# PSAT.net
KiCad netlist of a schematic drawn in Altium Designer
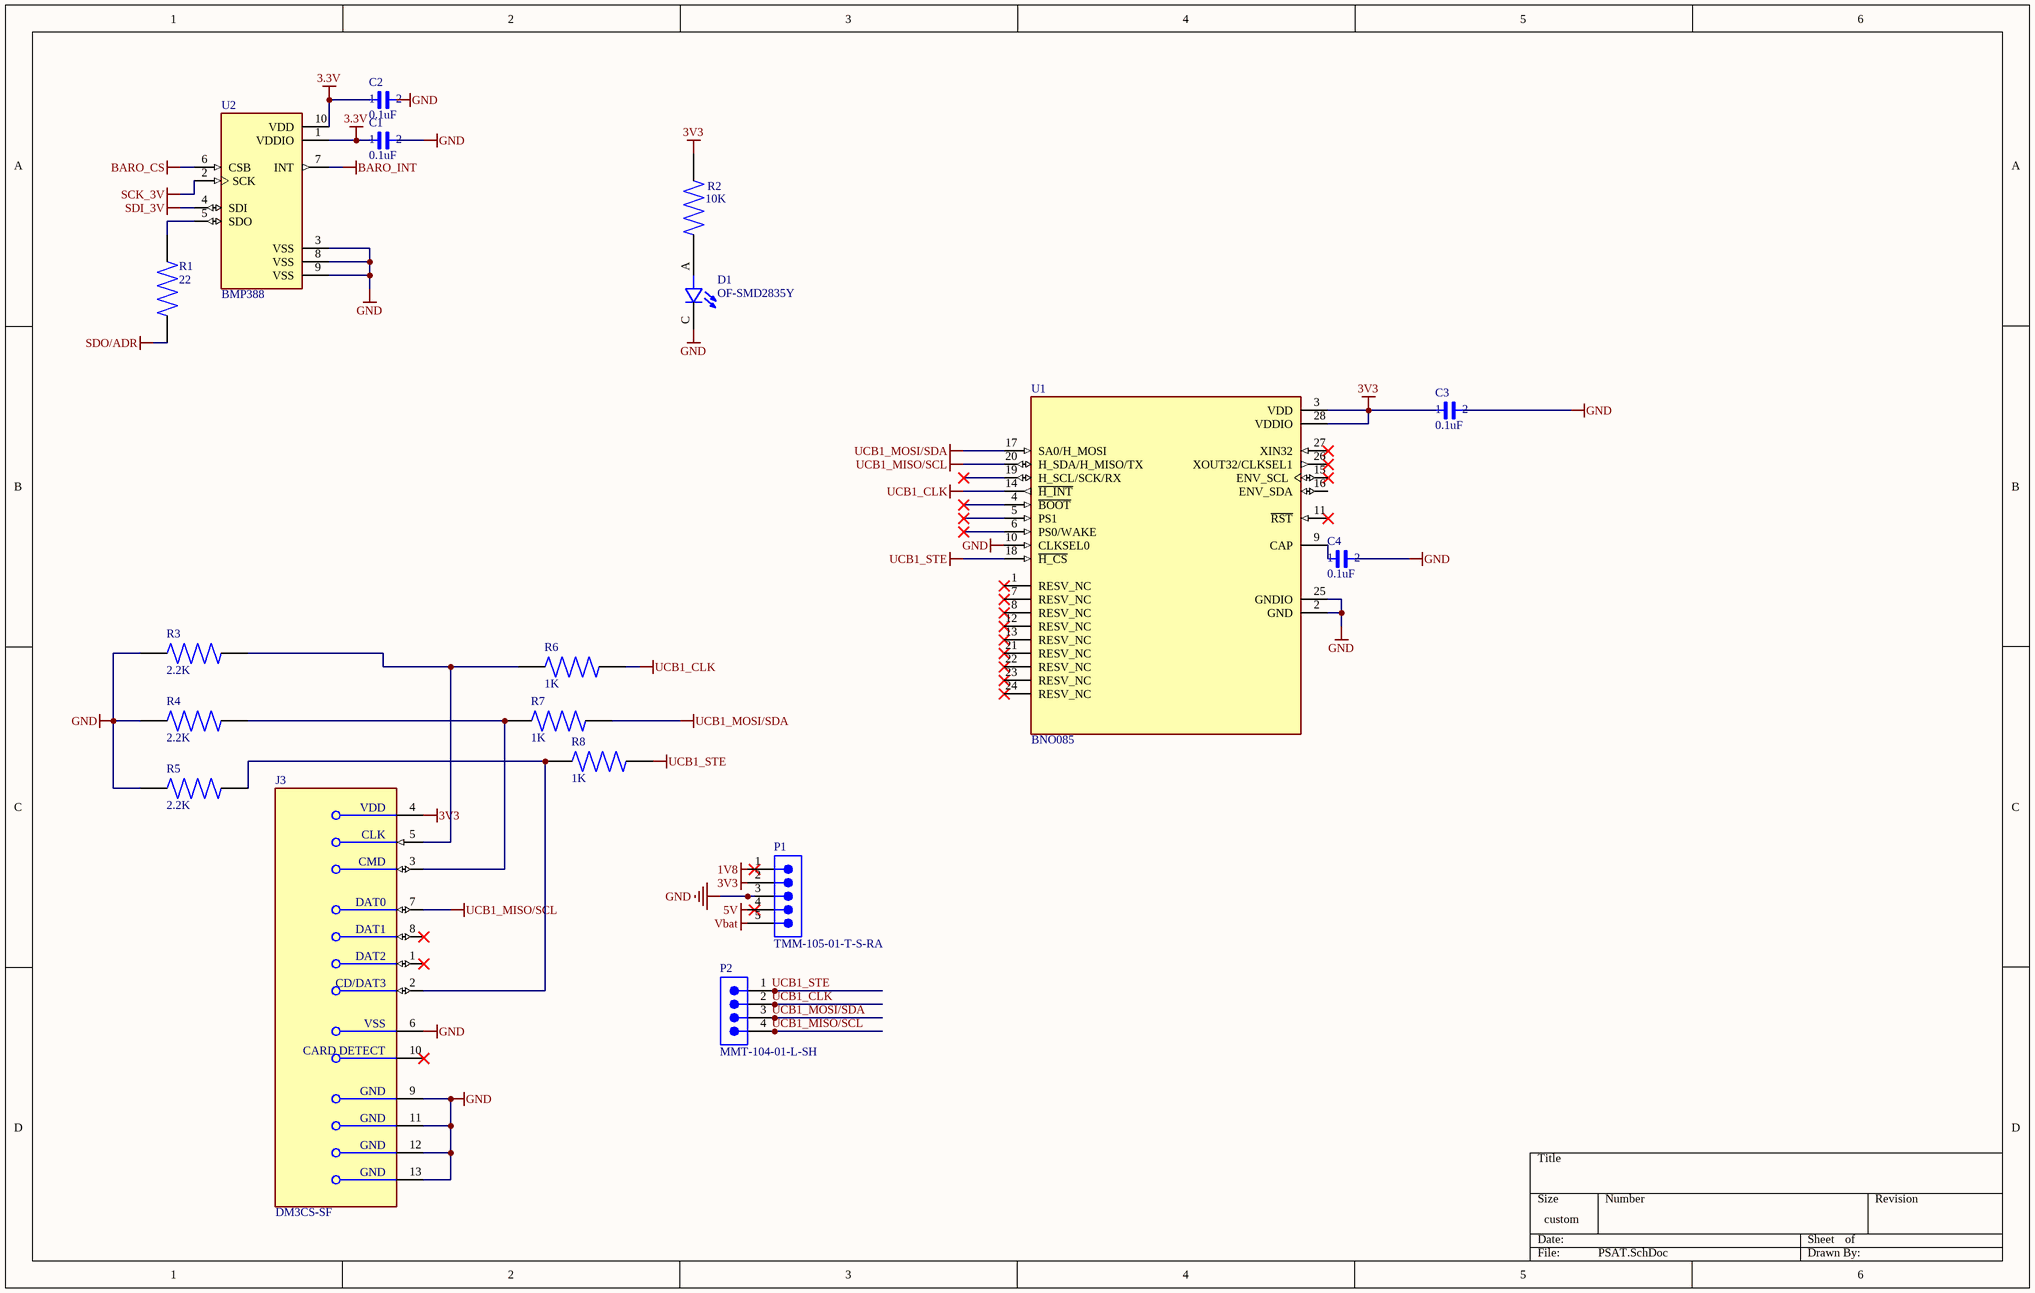
[diagram p0: PSAT.SchDoc]

(export (version "E")
  (design (tool "Eeschema 10.0.6"))
  (components
    (comp (ref "C1")
      (value "0.1uF")
      (footprint "0603")
      (description "0 Ohms Jumper 0.1W, 1/10W Chip Resistor 0603 (1608 Metric) Moisture Resistant Thick Film")
      (fields (field (name "MF") "Yageo") (field (name "MP") "C0603"))
      (libsource (lib "C0603") (part "C0603"))
    )
    (comp (ref "C2")
      (value "0.1uF")
      (footprint "0603")
      (description "0 Ohms Jumper 0.1W, 1/10W Chip Resistor 0603 (1608 Metric) Moisture Resistant Thick Film")
      (fields (field (name "MF") "Yageo") (field (name "MP") "C0603"))
      (libsource (lib "C0603") (part "C0603"))
    )
    (comp (ref "C3")
      (value "0.1uF")
      (footprint "0603")
      (description "0 Ohms Jumper 0.1W, 1/10W Chip Resistor 0603 (1608 Metric) Moisture Resistant Thick Film")
      (fields (field (name "MF") "Yageo") (field (name "MP") "C0603"))
      (libsource (lib "C0603") (part "C0603"))
    )
    (comp (ref "C4")
      (value "0.1uF")
      (footprint "0603")
      (description "0 Ohms Jumper 0.1W, 1/10W Chip Resistor 0603 (1608 Metric) Moisture Resistant Thick Film")
      (fields (field (name "MF") "Yageo") (field (name "MP") "C0603"))
      (libsource (lib "C0603") (part "C0603"))
    )
    (comp (ref "D1")
      (value "OF-SMD2835Y")
      (footprint "LED_OF-SMD2835Y")
      (description "LED; SMD; 2835, PLCC2; yellow; 2200-2800mcd; 2.8x3.5x0.75mm; 120Â°")
      (libsource (lib "OF-SMD2835Y") (part "OF-SMD2835Y"))
    )
    (comp (ref "J3")
      (value "DM3CS-SF")
      (footprint "FP-DM3CS-SF-MFG")
      (description "CONN MICRO SD CARD HINGED TYPE")
      (libsource (lib "Altium Content Vault") (part "bac915de5305cfdd1ca301aae530106"))
    )
    (comp (ref "P1")
      (value "TMM-105-01-T-S-RA")
      (footprint "SMTC-TMM-105-01-X-S-RA")
      (description "Low Profile Through-Hole Header, Right Angle, -55 to 105 degC, 2 mm Pitch, 5-Pin, Male, RoHS")
      (fields (field (name "MANUFACTURER") "Samtec"))
      (libsource (lib "Altium Content Vault") (part "SMTC-TMM-105-01-X-S-RA"))
    )
    (comp (ref "P2")
      (value "MMT-104-01-L-SH")
      (footprint "SMTC-MMT-104-01-X-SH")
      (description "Horizontal Surface Mount Header, -55 to 125 degC, 2 mm Pitch, 4-Pin, Male, RoHS")
      (fields (field (name "MANUFACTURER") "Samtec"))
      (libsource (lib "Altium Content Vault") (part "SMTC-MMT-104-X-X-SH"))
    )
    (comp (ref "R1")
      (value "22")
      (footprint "RESC1607X60N")
      (description "0 Ohms Jumper 0.1W, 1/10W Chip Resistor 0603 (1608 Metric) Moisture Resistant Thick Film")
      (fields (field (name "MF") "Yageo") (field (name "MP") "RC0603JR-070RL"))
      (libsource (lib "RC0603JR-070RL") (part "RC0603JR-070RL"))
    )
    (comp (ref "R2")
      (value "10K")
      (footprint "RESC1607X60N")
      (description "0 Ohms Jumper 0.1W, 1/10W Chip Resistor 0603 (1608 Metric) Moisture Resistant Thick Film")
      (fields (field (name "MF") "Yageo") (field (name "MP") "RC0603JR-070RL"))
      (libsource (lib "RC0603JR-070RL") (part "RC0603JR-070RL"))
    )
    (comp (ref "R3")
      (value "2.2K")
      (footprint "RESC1607X60N")
      (description "0 Ohms Jumper 0.1W, 1/10W Chip Resistor 0603 (1608 Metric) Moisture Resistant Thick Film")
      (fields (field (name "MF") "Yageo") (field (name "MP") "RC0603JR-070RL"))
      (libsource (lib "RC0603JR-070RL") (part "RC0603JR-070RL"))
    )
    (comp (ref "R4")
      (value "2.2K")
      (footprint "RESC1607X60N")
      (description "0 Ohms Jumper 0.1W, 1/10W Chip Resistor 0603 (1608 Metric) Moisture Resistant Thick Film")
      (fields (field (name "MF") "Yageo") (field (name "MP") "RC0603JR-070RL"))
      (libsource (lib "RC0603JR-070RL") (part "RC0603JR-070RL"))
    )
    (comp (ref "R5")
      (value "2.2K")
      (footprint "RESC1607X60N")
      (description "0 Ohms Jumper 0.1W, 1/10W Chip Resistor 0603 (1608 Metric) Moisture Resistant Thick Film")
      (fields (field (name "MF") "Yageo") (field (name "MP") "RC0603JR-070RL"))
      (libsource (lib "RC0603JR-070RL") (part "RC0603JR-070RL"))
    )
    (comp (ref "R6")
      (value "1K")
      (footprint "RESC1607X60N")
      (description "0 Ohms Jumper 0.1W, 1/10W Chip Resistor 0603 (1608 Metric) Moisture Resistant Thick Film")
      (fields (field (name "MF") "Yageo") (field (name "MP") "RC0603JR-070RL"))
      (libsource (lib "RC0603JR-070RL") (part "RC0603JR-070RL"))
    )
    (comp (ref "R7")
      (value "1K")
      (footprint "RESC1607X60N")
      (description "0 Ohms Jumper 0.1W, 1/10W Chip Resistor 0603 (1608 Metric) Moisture Resistant Thick Film")
      (fields (field (name "MF") "Yageo") (field (name "MP") "RC0603JR-070RL"))
      (libsource (lib "RC0603JR-070RL") (part "RC0603JR-070RL"))
    )
    (comp (ref "R8")
      (value "1K")
      (footprint "RESC1607X60N")
      (description "0 Ohms Jumper 0.1W, 1/10W Chip Resistor 0603 (1608 Metric) Moisture Resistant Thick Film")
      (fields (field (name "MF") "Yageo") (field (name "MP") "RC0603JR-070RL"))
      (libsource (lib "RC0603JR-070RL") (part "RC0603JR-070RL"))
    )
    (comp (ref "U1")
      (value "BNO085")
      (footprint "IC_BNO085")
      (description "Accelerometer, Gyroscope, Magnetometer, 9 Axis Sensor IÂ²C, SPI, UART Output")
      (fields (field (name "MF") "Hillcrest Laboratories,"))
      (libsource (lib "BNO085 (1)") (part "BNO085"))
    )
    (comp (ref "U2")
      (value "BMP388")
      (footprint "PQFN50P200X200X80-10N")
      (description "P-Sensor SPI I2C 1, 25 Bar SMD")
      (libsource (lib "BMP388") (part "BMP388"))
    )
  )
  (nets
    (net (code "2") (name "3.3V") (class "Default")
      (node (ref "C1") (pin "1") (pinfunction "1_1") (pintype "passive"))
      (node (ref "C2") (pin "1") (pinfunction "1_1") (pintype "passive"))
      (node (ref "U2") (pin "1") (pinfunction "VDDIO_1") (pintype "power_in"))
      (node (ref "U2") (pin "10") (pinfunction "VDD_10") (pintype "power_in"))
    )
    (net (code "3") (name "3V3") (class "Default")
      (node (ref "C3") (pin "1") (pinfunction "1_1") (pintype "passive"))
      (node (ref "J3") (pin "4") (pinfunction "VDD_4") (pintype "power_in"))
      (node (ref "R2") (pin "2") (pinfunction "2_2") (pintype "passive"))
      (node (ref "U1") (pin "28") (pinfunction "VDDIO_28") (pintype "power_in"))
      (node (ref "U1") (pin "3") (pinfunction "VDD_3") (pintype "power_in"))
    )
    (net (code "5") (name "BARO_CS") (class "Default")
      (node (ref "U2") (pin "6") (pinfunction "CSB_6") (pintype "input"))
    )
    (net (code "6") (name "BARO_INT") (class "Default")
      (node (ref "U2") (pin "7") (pinfunction "INT_7") (pintype "output"))
    )
    (net (code "7") (name "GND") (class "Default")
      (node (ref "C1") (pin "2") (pinfunction "2_2") (pintype "passive"))
      (node (ref "C2") (pin "2") (pinfunction "2_2") (pintype "passive"))
      (node (ref "C3") (pin "2") (pinfunction "2_2") (pintype "passive"))
      (node (ref "C4") (pin "2") (pinfunction "2_2") (pintype "passive"))
      (node (ref "D1") (pin "C") (pinfunction "C_C") (pintype "passive"))
      (node (ref "J3") (pin "11") (pinfunction "GND_11") (pintype "power_in"))
      (node (ref "J3") (pin "12") (pinfunction "GND_12") (pintype "power_in"))
      (node (ref "J3") (pin "13") (pinfunction "GND_13") (pintype "power_in"))
      (node (ref "J3") (pin "6") (pinfunction "VSS_6") (pintype "power_in"))
      (node (ref "J3") (pin "9") (pinfunction "GND_9") (pintype "power_in"))
      (node (ref "P1") (pin "3") (pinfunction "3_3") (pintype "passive"))
      (node (ref "R3") (pin "2") (pinfunction "2_2") (pintype "passive"))
      (node (ref "R4") (pin "2") (pinfunction "2_2") (pintype "passive"))
      (node (ref "R5") (pin "2") (pinfunction "2_2") (pintype "passive"))
      (node (ref "U1") (pin "10") (pinfunction "CLKSEL0_10") (pintype "input"))
      (node (ref "U1") (pin "2") (pinfunction "GND_2") (pintype "power_in"))
      (node (ref "U1") (pin "25") (pinfunction "GNDIO_25") (pintype "power_in"))
      (node (ref "U2") (pin "3") (pinfunction "VSS_3") (pintype "power_in"))
      (node (ref "U2") (pin "8") (pinfunction "VSS_8") (pintype "power_in"))
      (node (ref "U2") (pin "9") (pinfunction "VSS_9") (pintype "power_in"))
    )
    (net (code "8") (name "Net-(D1-PadA)") (class "Default")
      (node (ref "D1") (pin "A") (pinfunction "A_A") (pintype "passive"))
      (node (ref "R2") (pin "1") (pinfunction "1_1") (pintype "passive"))
    )
    (net (code "9") (name "Net-(J3-CD{slash}DAT3)") (class "Default")
      (node (ref "J3") (pin "2") (pinfunction "CD/DAT3_2") (pintype "bidirectional"))
      (node (ref "R5") (pin "1") (pinfunction "1_1") (pintype "passive"))
      (node (ref "R8") (pin "2") (pinfunction "2_2") (pintype "passive"))
    )
    (net (code "10") (name "Net-(J3-CLK)") (class "Default")
      (node (ref "J3") (pin "5") (pinfunction "CLK_5") (pintype "input"))
      (node (ref "R3") (pin "1") (pinfunction "1_1") (pintype "passive"))
      (node (ref "R6") (pin "2") (pinfunction "2_2") (pintype "passive"))
    )
    (net (code "11") (name "Net-(J3-CMD)") (class "Default")
      (node (ref "J3") (pin "3") (pinfunction "CMD_3") (pintype "bidirectional"))
      (node (ref "R4") (pin "1") (pinfunction "1_1") (pintype "passive"))
      (node (ref "R7") (pin "2") (pinfunction "2_2") (pintype "passive"))
    )
    (net (code "12") (name "Net-(U1-CAP)") (class "Default")
      (node (ref "C4") (pin "1") (pinfunction "1_1") (pintype "passive"))
      (node (ref "U1") (pin "9") (pinfunction "CAP_9") (pintype "passive"))
    )
    (net (code "13") (name "Net-(U2-SDO)") (class "Default")
      (node (ref "R1") (pin "2") (pinfunction "2_2") (pintype "passive"))
      (node (ref "U2") (pin "5") (pinfunction "SDO_5") (pintype "bidirectional"))
    )
    (net (code "14") (name "SCK_3V") (class "Default")
      (node (ref "U2") (pin "2") (pinfunction "SCK_2") (pintype "input"))
    )
    (net (code "15") (name "SDI_3V") (class "Default")
      (node (ref "U2") (pin "4") (pinfunction "SDI_4") (pintype "bidirectional"))
    )
    (net (code "16") (name "SDO{slash}ADR") (class "Default")
      (node (ref "R1") (pin "1") (pinfunction "1_1") (pintype "passive"))
    )
    (net (code "17") (name "UCB1_CLK") (class "Default")
      (node (ref "P2") (pin "2") (pinfunction "2_2") (pintype "passive"))
      (node (ref "R6") (pin "1") (pinfunction "1_1") (pintype "passive"))
      (node (ref "U1") (pin "14") (pinfunction "~{H_INT}_14") (pintype "output"))
    )
    (net (code "18") (name "UCB1_MISO{slash}SCL") (class "Default")
      (node (ref "J3") (pin "7") (pinfunction "DAT0_7") (pintype "bidirectional"))
      (node (ref "P2") (pin "4") (pinfunction "4_4") (pintype "passive"))
      (node (ref "U1") (pin "20") (pinfunction "H_SDA/H_MISO/TX_20") (pintype "bidirectional"))
    )
    (net (code "19") (name "UCB1_MOSI{slash}SDA") (class "Default")
      (node (ref "P2") (pin "3") (pinfunction "3_3") (pintype "passive"))
      (node (ref "R7") (pin "1") (pinfunction "1_1") (pintype "passive"))
      (node (ref "U1") (pin "17") (pinfunction "SA0/H_MOSI_17") (pintype "input"))
    )
    (net (code "20") (name "UCB1_STE") (class "Default")
      (node (ref "P2") (pin "1") (pinfunction "1_1") (pintype "passive"))
      (node (ref "R8") (pin "1") (pinfunction "1_1") (pintype "passive"))
      (node (ref "U1") (pin "18") (pinfunction "~{H_CS}_18") (pintype "input"))
    )
    (net (code "22") (name "unconnected-(J3-CARD_DETECT-Pad10)") (class "Default")
      (node (ref "J3") (pin "10") (pinfunction "CARD_DETECT_10") (pintype "passive+no_connect"))
    )
    (net (code "23") (name "unconnected-(J3-DAT1-Pad8)") (class "Default")
      (node (ref "J3") (pin "8") (pinfunction "DAT1_8") (pintype "bidirectional+no_connect"))
    )
    (net (code "24") (name "unconnected-(J3-DAT2-Pad1)") (class "Default")
      (node (ref "J3") (pin "1") (pinfunction "DAT2_1") (pintype "bidirectional+no_connect"))
    )
    (net (code "25") (name "unconnected-(P1-Pad1)") (class "Default")
      (node (ref "P1") (pin "1") (pinfunction "1_1") (pintype "passive"))
    )
    (net (code "26") (name "unconnected-(P1-Pad2)") (class "Default")
      (node (ref "P1") (pin "2") (pinfunction "2_2") (pintype "passive"))
    )
    (net (code "27") (name "unconnected-(P1-Pad4)") (class "Default")
      (node (ref "P1") (pin "4") (pinfunction "4_4") (pintype "passive"))
    )
    (net (code "28") (name "unconnected-(P1-Pad5)") (class "Default")
      (node (ref "P1") (pin "5") (pinfunction "5_5") (pintype "passive"))
    )
    (net (code "29") (name "unconnected-(U1-ENV_SCL-Pad15)") (class "Default")
      (node (ref "U1") (pin "15") (pinfunction "ENV_SCL_15") (pintype "bidirectional+no_connect"))
    )
    (net (code "30") (name "unconnected-(U1-ENV_SDA-Pad16)") (class "Default")
      (node (ref "U1") (pin "16") (pinfunction "ENV_SDA_16") (pintype "bidirectional"))
    )
    (net (code "31") (name "unconnected-(U1-H_SCL{slash}SCK{slash}RX-Pad19)") (class "Default")
      (node (ref "U1") (pin "19") (pinfunction "H_SCL/SCK/RX_19") (pintype "bidirectional+no_connect"))
    )
    (net (code "32") (name "unconnected-(U1-PS0{slash}WAKE-Pad6)") (class "Default")
      (node (ref "U1") (pin "6") (pinfunction "PS0/WAKE_6") (pintype "input+no_connect"))
    )
    (net (code "33") (name "unconnected-(U1-PS1-Pad5)") (class "Default")
      (node (ref "U1") (pin "5") (pinfunction "PS1_5") (pintype "input+no_connect"))
    )
    (net (code "34") (name "unconnected-(U1-RESV_NC-Pad1)") (class "Default")
      (node (ref "U1") (pin "1") (pinfunction "RESV_NC_1") (pintype "passive+no_connect"))
    )
    (net (code "35") (name "unconnected-(U1-RESV_NC-Pad7)") (class "Default")
      (node (ref "U1") (pin "7") (pinfunction "RESV_NC_7") (pintype "passive+no_connect"))
    )
    (net (code "36") (name "unconnected-(U1-RESV_NC-Pad8)") (class "Default")
      (node (ref "U1") (pin "8") (pinfunction "RESV_NC_8") (pintype "passive+no_connect"))
    )
    (net (code "37") (name "unconnected-(U1-RESV_NC-Pad12)") (class "Default")
      (node (ref "U1") (pin "12") (pinfunction "RESV_NC_12") (pintype "passive+no_connect"))
    )
    (net (code "38") (name "unconnected-(U1-RESV_NC-Pad13)") (class "Default")
      (node (ref "U1") (pin "13") (pinfunction "RESV_NC_13") (pintype "passive+no_connect"))
    )
    (net (code "39") (name "unconnected-(U1-RESV_NC-Pad21)") (class "Default")
      (node (ref "U1") (pin "21") (pinfunction "RESV_NC_21") (pintype "passive+no_connect"))
    )
    (net (code "40") (name "unconnected-(U1-RESV_NC-Pad22)") (class "Default")
      (node (ref "U1") (pin "22") (pinfunction "RESV_NC_22") (pintype "passive+no_connect"))
    )
    (net (code "41") (name "unconnected-(U1-RESV_NC-Pad23)") (class "Default")
      (node (ref "U1") (pin "23") (pinfunction "RESV_NC_23") (pintype "passive+no_connect"))
    )
    (net (code "42") (name "unconnected-(U1-RESV_NC-Pad24)") (class "Default")
      (node (ref "U1") (pin "24") (pinfunction "RESV_NC_24") (pintype "passive+no_connect"))
    )
    (net (code "43") (name "unconnected-(U1-XIN32-Pad27)") (class "Default")
      (node (ref "U1") (pin "27") (pinfunction "XIN32_27") (pintype "input+no_connect"))
    )
    (net (code "44") (name "unconnected-(U1-XOUT32{slash}CLKSEL1-Pad26)") (class "Default")
      (node (ref "U1") (pin "26") (pinfunction "XOUT32/CLKSEL1_26") (pintype "output+no_connect"))
    )
    (net (code "45") (name "unconnected-(U1-~{BOOT}-Pad4)") (class "Default")
      (node (ref "U1") (pin "4") (pinfunction "~{BOOT}_4") (pintype "input+no_connect"))
    )
    (net (code "46") (name "unconnected-(U1-~{RST}-Pad11)") (class "Default")
      (node (ref "U1") (pin "11") (pinfunction "~{RST}_11") (pintype "input+no_connect"))
    )
  )
)
